# DMX_isolated_V2_single-sided.net
KiCad netlist of a schematic drawn in EAGLE
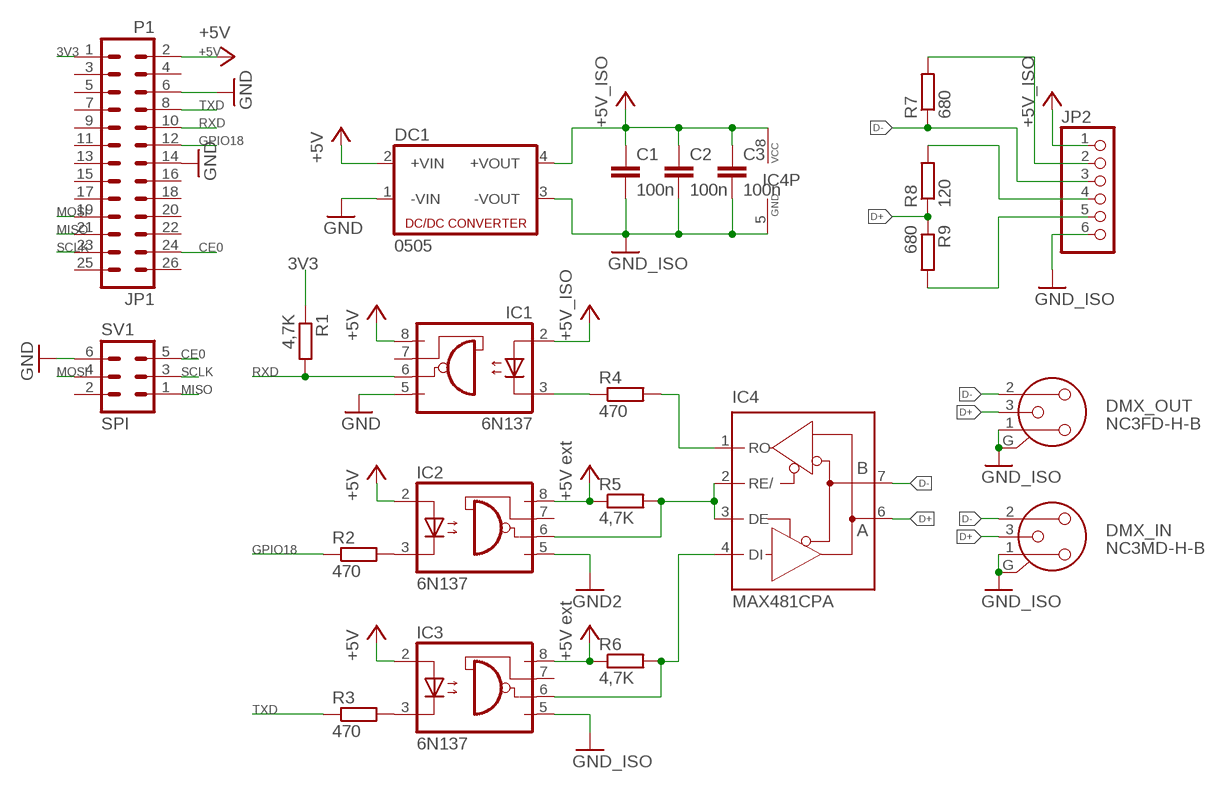
[diagram p0: schematic, sheet 1]

(export (version "E")
  (design (tool "Eeschema 10.0.6"))
  (components
    (comp (ref "C1")
      (value "100n")
      (footprint "eagle-import:C050-024X044")
      (libsource (lib "eagle-import") (part "C-EU050-024X044"))
    )
    (comp (ref "C2")
      (value "100n")
      (footprint "eagle-import:C050-024X044")
      (libsource (lib "eagle-import") (part "C-EU050-024X044"))
    )
    (comp (ref "C3")
      (value "100n")
      (footprint "eagle-import:C050-024X044")
      (libsource (lib "eagle-import") (part "C-EU050-024X044"))
    )
    (comp (ref "DC1")
      (value "0505")
      (footprint "eagle-import:NME")
      (fields (field (name "MF") "C & D TECHNOLOGIES, INC") (field (name "MPN") "NME1205D"))
      (libsource (lib "eagle-import") (part "NME"))
    )
    (comp (ref "DMX_IN")
      (value "NC3MD-H-B")
      (footprint "eagle-import:NC3MD-H-B")
      (libsource (lib "eagle-import") (part "NC3MD-H-B"))
    )
    (comp (ref "DMX_OUT")
      (value "NC3FD-H-B")
      (footprint "eagle-import:NC3FD-H-B")
      (libsource (lib "eagle-import") (part "NC3FD-H-B"))
    )
    (comp (ref "IC1")
      (value "6N137")
      (footprint "eagle-import:DIL08")
      (libsource (lib "eagle-import") (part "6N137"))
    )
    (comp (ref "IC2")
      (value "6N137")
      (footprint "eagle-import:DIL08")
      (libsource (lib "eagle-import") (part "6N137"))
    )
    (comp (ref "IC3")
      (value "6N137")
      (footprint "eagle-import:DIL08")
      (libsource (lib "eagle-import") (part "6N137"))
    )
    (comp (ref "IC4")
      (value "MAX481CPA")
      (footprint "eagle-import:DIL08")
      (fields (field (name "MPN") "MAX481CPA+"))
      (libsource (lib "eagle-import") (part "MAX481CPA"))
    )
    (comp (ref "JP1")
      (value "P1")
      (footprint "eagle-import:MA13-2")
      (libsource (lib "eagle-import") (part "MA13-2"))
    )
    (comp (ref "JP2")
      (value "PINHD-1X6")
      (footprint "eagle-import:1X06")
      (libsource (lib "eagle-import") (part "PINHD-1X6"))
    )
    (comp (ref "R1")
      (value "4,7K")
      (footprint "eagle-import:0204V")
      (libsource (lib "eagle-import") (part "R-EU_0204/2V"))
    )
    (comp (ref "R2")
      (value "470")
      (footprint "eagle-import:0204V")
      (libsource (lib "eagle-import") (part "R-EU_0204/2V"))
    )
    (comp (ref "R3")
      (value "470")
      (footprint "eagle-import:0204V")
      (libsource (lib "eagle-import") (part "R-EU_0204/2V"))
    )
    (comp (ref "R4")
      (value "470")
      (footprint "eagle-import:0204V")
      (libsource (lib "eagle-import") (part "R-EU_0204/2V"))
    )
    (comp (ref "R5")
      (value "4,7K")
      (footprint "eagle-import:0204V")
      (libsource (lib "eagle-import") (part "R-EU_0204/2V"))
    )
    (comp (ref "R6")
      (value "4,7K")
      (footprint "eagle-import:0204V")
      (libsource (lib "eagle-import") (part "R-EU_0204/2V"))
    )
    (comp (ref "R7")
      (value "680")
      (footprint "eagle-import:0204V")
      (libsource (lib "eagle-import") (part "R-EU_0204/2V"))
    )
    (comp (ref "R8")
      (value "120")
      (footprint "eagle-import:0204V")
      (libsource (lib "eagle-import") (part "R-EU_0204/2V"))
    )
    (comp (ref "R9")
      (value "680")
      (footprint "eagle-import:0204V")
      (libsource (lib "eagle-import") (part "R-EU_0204/2V"))
    )
    (comp (ref "SV1")
      (value "SPI")
      (footprint "eagle-import:MA03-2")
      (libsource (lib "eagle-import") (part "MA03-2"))
    )
  )
  (nets
    (net (code "1") (name "+5V") (class "Default")
      (node (ref "DC1") (pin "2") (pinfunction "+VIN_2") (pintype "passive"))
      (node (ref "IC1") (pin "8") (pinfunction "VCC_8") (pintype "passive"))
      (node (ref "IC2") (pin "2") (pinfunction "A_2") (pintype "passive"))
      (node (ref "IC3") (pin "2") (pinfunction "A_2") (pintype "passive"))
      (node (ref "JP1") (pin "2") (pinfunction "2_2") (pintype "passive"))
    )
    (net (code "2") (name "+5V ext") (class "Default")
      (node (ref "C1") (pin "1") (pinfunction "1_1") (pintype "passive"))
      (node (ref "C2") (pin "1") (pinfunction "1_1") (pintype "passive"))
      (node (ref "C3") (pin "1") (pinfunction "1_1") (pintype "passive"))
      (node (ref "DC1") (pin "4") (pinfunction "+VOUT_4") (pintype "passive"))
      (node (ref "IC1") (pin "2") (pinfunction "A_2") (pintype "passive"))
      (node (ref "IC2") (pin "8") (pinfunction "VCC_8") (pintype "passive"))
      (node (ref "IC3") (pin "8") (pinfunction "VCC_8") (pintype "passive"))
      (node (ref "IC4") (pin "8") (pinfunction "VCC_8") (pintype "power_in"))
      (node (ref "JP2") (pin "1") (pinfunction "1_1") (pintype "passive"))
      (node (ref "R5") (pin "1") (pinfunction "1_1") (pintype "passive"))
      (node (ref "R6") (pin "1") (pinfunction "1_1") (pintype "passive"))
    )
    (net (code "3") (name "/3V3") (class "Default")
      (node (ref "JP1") (pin "1") (pinfunction "1_1") (pintype "passive"))
      (node (ref "R1") (pin "1") (pinfunction "1_1") (pintype "passive"))
    )
    (net (code "4") (name "/CE0") (class "Default")
      (node (ref "JP1") (pin "24") (pinfunction "24_24") (pintype "passive"))
      (node (ref "SV1") (pin "5") (pinfunction "5_5") (pintype "passive"))
    )
    (net (code "5") (name "/GPIO18") (class "Default")
      (node (ref "JP1") (pin "12") (pinfunction "12_12") (pintype "passive"))
      (node (ref "R2") (pin "1") (pinfunction "1_1") (pintype "passive"))
    )
    (net (code "6") (name "/MISO") (class "Default")
      (node (ref "JP1") (pin "21") (pinfunction "21_21") (pintype "passive"))
      (node (ref "SV1") (pin "1") (pinfunction "1_1") (pintype "passive"))
    )
    (net (code "7") (name "/MOSI") (class "Default")
      (node (ref "JP1") (pin "19") (pinfunction "19_19") (pintype "passive"))
      (node (ref "SV1") (pin "4") (pinfunction "4_4") (pintype "passive"))
    )
    (net (code "8") (name "/RXD") (class "Default")
      (node (ref "IC1") (pin "6") (pinfunction "VO_6") (pintype "passive"))
      (node (ref "JP1") (pin "10") (pinfunction "10_10") (pintype "passive"))
      (node (ref "R1") (pin "2") (pinfunction "2_2") (pintype "passive"))
    )
    (net (code "9") (name "/SCLK") (class "Default")
      (node (ref "JP1") (pin "23") (pinfunction "23_23") (pintype "passive"))
      (node (ref "SV1") (pin "3") (pinfunction "3_3") (pintype "passive"))
    )
    (net (code "10") (name "/TXD") (class "Default")
      (node (ref "JP1") (pin "8") (pinfunction "8_8") (pintype "passive"))
      (node (ref "R3") (pin "1") (pinfunction "1_1") (pintype "passive"))
    )
    (net (code "11") (name "D+") (class "Default")
      (node (ref "DMX_IN") (pin "3") (pinfunction "3_3") (pintype "passive"))
      (node (ref "DMX_OUT") (pin "3") (pinfunction "3_3") (pintype "passive"))
      (node (ref "IC4") (pin "6") (pinfunction "A_6") (pintype "passive"))
      (node (ref "R8") (pin "1") (pinfunction "1_1") (pintype "passive"))
      (node (ref "R9") (pin "1") (pinfunction "1_1") (pintype "passive"))
    )
    (net (code "12") (name "D-") (class "Default")
      (node (ref "DMX_IN") (pin "2") (pinfunction "1_2") (pintype "passive"))
      (node (ref "DMX_OUT") (pin "2") (pinfunction "1_2") (pintype "passive"))
      (node (ref "IC4") (pin "7") (pinfunction "B_7") (pintype "passive"))
      (node (ref "JP2") (pin "3") (pinfunction "3_3") (pintype "passive"))
      (node (ref "R7") (pin "1") (pinfunction "1_1") (pintype "passive"))
    )
    (net (code "13") (name "GND") (class "Default")
      (node (ref "DC1") (pin "1") (pinfunction "-VIN_1") (pintype "passive"))
      (node (ref "IC1") (pin "5") (pinfunction "GND_5") (pintype "passive"))
      (node (ref "JP1") (pin "14") (pinfunction "14_14") (pintype "passive"))
      (node (ref "JP1") (pin "6") (pinfunction "6_6") (pintype "passive"))
      (node (ref "SV1") (pin "6") (pinfunction "6_6") (pintype "passive"))
    )
    (net (code "14") (name "GND2") (class "Default")
      (node (ref "C1") (pin "2") (pinfunction "2_2") (pintype "passive"))
      (node (ref "C2") (pin "2") (pinfunction "2_2") (pintype "passive"))
      (node (ref "C3") (pin "2") (pinfunction "2_2") (pintype "passive"))
      (node (ref "DC1") (pin "3") (pinfunction "-VOUT_3") (pintype "passive"))
      (node (ref "DMX_IN") (pin "1") (pinfunction "2_1") (pintype "passive"))
      (node (ref "DMX_IN") (pin "G") (pinfunction "G_G") (pintype "passive"))
      (node (ref "DMX_OUT") (pin "1") (pinfunction "2_1") (pintype "passive"))
      (node (ref "DMX_OUT") (pin "G") (pinfunction "G_G") (pintype "passive"))
      (node (ref "IC2") (pin "5") (pinfunction "GND_5") (pintype "passive"))
      (node (ref "IC3") (pin "5") (pinfunction "GND_5") (pintype "passive"))
      (node (ref "IC4") (pin "5") (pinfunction "GND_5") (pintype "power_in"))
      (node (ref "JP2") (pin "6") (pinfunction "6_6") (pintype "passive"))
    )
    (net (code "15") (name "Net-(IC1-C)") (class "Default")
      (node (ref "IC1") (pin "3") (pinfunction "C_3") (pintype "passive"))
      (node (ref "R4") (pin "1") (pinfunction "1_1") (pintype "passive"))
    )
    (net (code "16") (name "Net-(IC2-C)") (class "Default")
      (node (ref "IC2") (pin "3") (pinfunction "C_3") (pintype "passive"))
      (node (ref "R2") (pin "2") (pinfunction "2_2") (pintype "passive"))
    )
    (net (code "17") (name "Net-(IC2-VO)") (class "Default")
      (node (ref "IC2") (pin "6") (pinfunction "VO_6") (pintype "passive"))
      (node (ref "IC4") (pin "2") (pinfunction "RE/_2") (pintype "input"))
      (node (ref "IC4") (pin "3") (pinfunction "DE_3") (pintype "input"))
      (node (ref "R5") (pin "2") (pinfunction "2_2") (pintype "passive"))
    )
    (net (code "18") (name "Net-(IC3-C)") (class "Default")
      (node (ref "IC3") (pin "3") (pinfunction "C_3") (pintype "passive"))
      (node (ref "R3") (pin "2") (pinfunction "2_2") (pintype "passive"))
    )
    (net (code "19") (name "Net-(IC3-VO)") (class "Default")
      (node (ref "IC3") (pin "6") (pinfunction "VO_6") (pintype "passive"))
      (node (ref "IC4") (pin "4") (pinfunction "DI_4") (pintype "input"))
      (node (ref "R6") (pin "2") (pinfunction "2_2") (pintype "passive"))
    )
    (net (code "20") (name "Net-(IC4A-RO)") (class "Default")
      (node (ref "IC4") (pin "1") (pinfunction "RO_1") (pintype "output"))
      (node (ref "R4") (pin "2") (pinfunction "2_2") (pintype "passive"))
    )
    (net (code "21") (name "Net-(JP2-Pad2)") (class "Default")
      (node (ref "JP2") (pin "2") (pinfunction "2_2") (pintype "passive"))
      (node (ref "R7") (pin "2") (pinfunction "2_2") (pintype "passive"))
    )
    (net (code "22") (name "Net-(JP2-Pad4)") (class "Default")
      (node (ref "JP2") (pin "4") (pinfunction "4_4") (pintype "passive"))
      (node (ref "R8") (pin "2") (pinfunction "2_2") (pintype "passive"))
    )
    (net (code "23") (name "Net-(JP2-Pad5)") (class "Default")
      (node (ref "JP2") (pin "5") (pinfunction "5_5") (pintype "passive"))
      (node (ref "R9") (pin "2") (pinfunction "2_2") (pintype "passive"))
    )
    (net (code "24") (name "unconnected-(IC1-VE-Pad7)") (class "Default")
      (node (ref "IC1") (pin "7") (pinfunction "VE_7") (pintype "passive"))
    )
    (net (code "25") (name "unconnected-(IC2-VE-Pad7)") (class "Default")
      (node (ref "IC2") (pin "7") (pinfunction "VE_7") (pintype "passive"))
    )
    (net (code "26") (name "unconnected-(IC3-VE-Pad7)") (class "Default")
      (node (ref "IC3") (pin "7") (pinfunction "VE_7") (pintype "passive"))
    )
    (net (code "27") (name "unconnected-(JP1-Pad3)") (class "Default")
      (node (ref "JP1") (pin "3") (pinfunction "3_3") (pintype "passive"))
    )
    (net (code "28") (name "unconnected-(JP1-Pad4)") (class "Default")
      (node (ref "JP1") (pin "4") (pinfunction "4_4") (pintype "passive"))
    )
    (net (code "29") (name "unconnected-(JP1-Pad5)") (class "Default")
      (node (ref "JP1") (pin "5") (pinfunction "5_5") (pintype "passive"))
    )
    (net (code "30") (name "unconnected-(JP1-Pad7)") (class "Default")
      (node (ref "JP1") (pin "7") (pinfunction "7_7") (pintype "passive"))
    )
    (net (code "31") (name "unconnected-(JP1-Pad9)") (class "Default")
      (node (ref "JP1") (pin "9") (pinfunction "9_9") (pintype "passive"))
    )
    (net (code "32") (name "unconnected-(JP1-Pad11)") (class "Default")
      (node (ref "JP1") (pin "11") (pinfunction "11_11") (pintype "passive"))
    )
    (net (code "33") (name "unconnected-(JP1-Pad13)") (class "Default")
      (node (ref "JP1") (pin "13") (pinfunction "13_13") (pintype "passive"))
    )
    (net (code "34") (name "unconnected-(JP1-Pad15)") (class "Default")
      (node (ref "JP1") (pin "15") (pinfunction "15_15") (pintype "passive"))
    )
    (net (code "35") (name "unconnected-(JP1-Pad16)") (class "Default")
      (node (ref "JP1") (pin "16") (pinfunction "16_16") (pintype "passive"))
    )
    (net (code "36") (name "unconnected-(JP1-Pad17)") (class "Default")
      (node (ref "JP1") (pin "17") (pinfunction "17_17") (pintype "passive"))
    )
    (net (code "37") (name "unconnected-(JP1-Pad18)") (class "Default")
      (node (ref "JP1") (pin "18") (pinfunction "18_18") (pintype "passive"))
    )
    (net (code "38") (name "unconnected-(JP1-Pad20)") (class "Default")
      (node (ref "JP1") (pin "20") (pinfunction "20_20") (pintype "passive"))
    )
    (net (code "39") (name "unconnected-(JP1-Pad22)") (class "Default")
      (node (ref "JP1") (pin "22") (pinfunction "22_22") (pintype "passive"))
    )
    (net (code "40") (name "unconnected-(JP1-Pad25)") (class "Default")
      (node (ref "JP1") (pin "25") (pinfunction "25_25") (pintype "passive"))
    )
    (net (code "41") (name "unconnected-(JP1-Pad26)") (class "Default")
      (node (ref "JP1") (pin "26") (pinfunction "26_26") (pintype "passive"))
    )
    (net (code "42") (name "unconnected-(SV1-Pad2)") (class "Default")
      (node (ref "SV1") (pin "2") (pinfunction "2_2") (pintype "passive"))
    )
  )
)
